# DDS9m-Controller.net
KiCad netlist of a schematic drawn in EAGLE
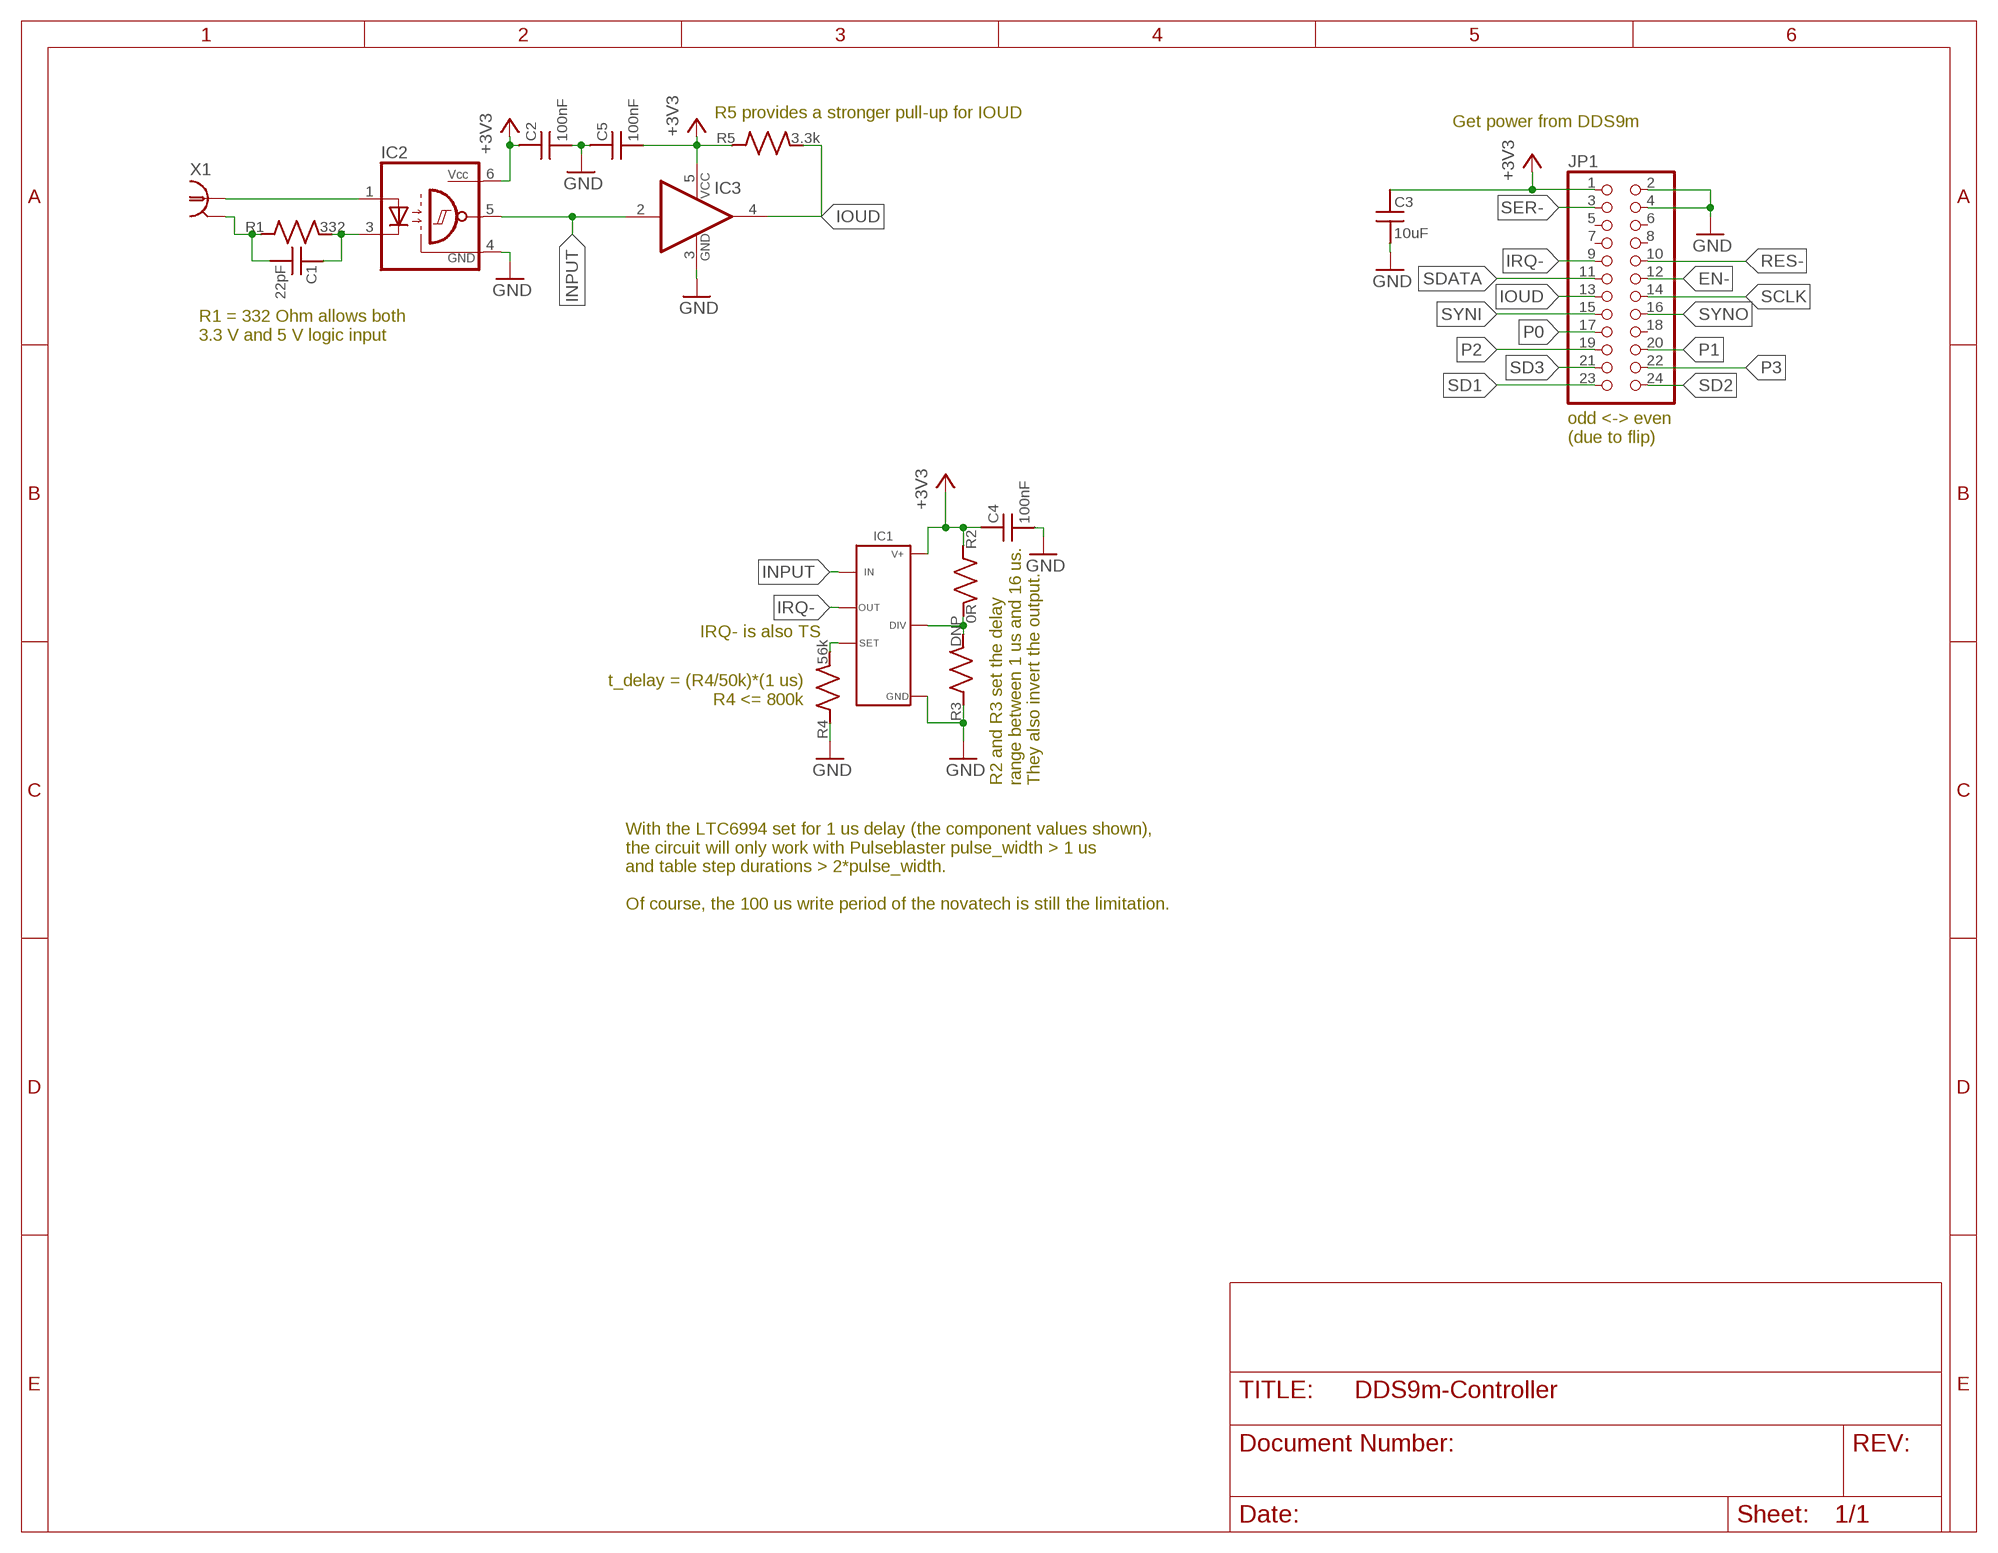
[diagram p0: schematic, sheet 1]

(export (version "E")
  (design (tool "Eeschema 10.0.6"))
  (components
    (comp (ref "C1")
      (value "22pF")
      (footprint "eagle-import:C_MLCC_0402")
      (fields (field (name "PARTNO") "CL05C220JB51PNC"))
      (libsource (lib "eagle-import") (part "C_MLCC_SMDCMLCC_0402"))
    )
    (comp (ref "C2")
      (value "100nF")
      (footprint "eagle-import:C_MLCC_0603")
      (fields (field (name "PARTNO") "CL10B104KB8NNNC"))
      (libsource (lib "eagle-import") (part "C_MLCC_SMDCMLCC_0603"))
    )
    (comp (ref "C3")
      (value "10uF")
      (footprint "eagle-import:C_MLCC_1210")
      (fields (field (name "PARTNO") "CL32B106KLJNNNE"))
      (libsource (lib "eagle-import") (part "C_MLCC_SMDCMLCC_1210"))
    )
    (comp (ref "C4")
      (value "100nF")
      (footprint "eagle-import:C_MLCC_0603")
      (fields (field (name "PARTNO") "CL10B104KB8NNNC"))
      (libsource (lib "eagle-import") (part "C_MLCC_SMDCMLCC_0603"))
    )
    (comp (ref "C5")
      (value "100nF")
      (footprint "eagle-import:C_MLCC_0603")
      (fields (field (name "PARTNO") "CL10B104KB8NNNC"))
      (libsource (lib "eagle-import") (part "C_MLCC_SMDCMLCC_0603"))
    )
    (comp (ref "IC1")
      (value "LTC6994-X")
      (footprint "eagle-import:SOT23-6L")
      (fields (field (name "PARTNO") "LTC6994IS6-2#TRMPBF"))
      (libsource (lib "eagle-import") (part "LTC6994-X"))
    )
    (comp (ref "IC2")
      (value "TLP2767")
      (footprint "eagle-import:SO6L")
      (fields (field (name "PARTNO") "TLP2767(TP,E"))
      (libsource (lib "eagle-import") (part "TLP2767"))
    )
    (comp (ref "IC3")
      (value "74LVC1G07DCK")
      (footprint "eagle-import:SC70-5")
      (fields (field (name "PARTNO") "SN74LVC1G07DCKR"))
      (libsource (lib "eagle-import") (part "741G07DCKLVC"))
    )
    (comp (ref "JP1")
      (value "PINHD-2X12")
      (footprint "eagle-import:2X12")
      (fields (field (name "PARTNO") "PPPC122LFBN-RC"))
      (libsource (lib "eagle-import") (part "PINHD-2X12"))
    )
    (comp (ref "R1")
      (value "332")
      (footprint "eagle-import:R_0603")
      (fields (field (name "PARTNO") "ERJ-3EKF3320V"))
      (libsource (lib "eagle-import") (part "R_SMDR0603"))
    )
    (comp (ref "R2")
      (value "0R")
      (footprint "eagle-import:R_0603")
      (fields (field (name "PARTNO") "MF-RES-0603-0"))
      (libsource (lib "eagle-import") (part "R_SMDR0603"))
    )
    (comp (ref "R3")
      (value "DNP")
      (footprint "eagle-import:R_0603")
      (libsource (lib "eagle-import") (part "R_SMDR0603"))
    )
    (comp (ref "R4")
      (value "56k")
      (footprint "eagle-import:R_0603")
      (fields (field (name "PARTNO") "ERA-3AEB563V"))
      (libsource (lib "eagle-import") (part "R_SMDR0603"))
    )
    (comp (ref "R5")
      (value "3.3k")
      (footprint "eagle-import:R_0603")
      (fields (field (name "PARTNO") "ERJ-3EKF3301V"))
      (libsource (lib "eagle-import") (part "R_SMDR0603"))
    )
    (comp (ref "X1")
      (value "BNC-V")
      (footprint "eagle-import:BNC-V")
      (fields (field (name "PARTNO") "5227222-3"))
      (libsource (lib "eagle-import") (part "BNC-V"))
    )
  )
  (nets
    (net (code "1") (name "+3V3") (class "Default")
      (node (ref "C2") (pin "P$1") (pinfunction "1_P$1") (pintype "passive"))
      (node (ref "C3") (pin "P$1") (pinfunction "1_P$1") (pintype "passive"))
      (node (ref "C4") (pin "P$1") (pinfunction "1_P$1") (pintype "passive"))
      (node (ref "C5") (pin "P$2") (pinfunction "2_P$2") (pintype "passive"))
      (node (ref "IC1") (pin "5") (pinfunction "V+_5") (pintype "input"))
      (node (ref "IC2") (pin "6") (pinfunction "VCC_6") (pintype "passive"))
      (node (ref "IC3") (pin "5") (pinfunction "VCC_5") (pintype "power_in"))
      (node (ref "JP1") (pin "1") (pinfunction "1_1") (pintype "passive"))
      (node (ref "R2") (pin "P$1") (pinfunction "1_P$1") (pintype "passive"))
      (node (ref "R5") (pin "P$1") (pinfunction "1_P$1") (pintype "passive"))
    )
    (net (code "2") (name "EN-") (class "Default")
      (node (ref "JP1") (pin "12") (pinfunction "12_12") (pintype "passive"))
    )
    (net (code "3") (name "GND") (class "Default")
      (node (ref "C2") (pin "P$2") (pinfunction "2_P$2") (pintype "passive"))
      (node (ref "C3") (pin "P$2") (pinfunction "2_P$2") (pintype "passive"))
      (node (ref "C4") (pin "P$2") (pinfunction "2_P$2") (pintype "passive"))
      (node (ref "C5") (pin "P$1") (pinfunction "1_P$1") (pintype "passive"))
      (node (ref "IC1") (pin "2") (pinfunction "GND_2") (pintype "input"))
      (node (ref "IC2") (pin "4") (pinfunction "GND_4") (pintype "passive"))
      (node (ref "IC3") (pin "3") (pinfunction "GND_3") (pintype "power_in"))
      (node (ref "JP1") (pin "2") (pinfunction "2_2") (pintype "passive"))
      (node (ref "JP1") (pin "4") (pinfunction "4_4") (pintype "passive"))
      (node (ref "R3") (pin "P$1") (pinfunction "1_P$1") (pintype "passive"))
      (node (ref "R4") (pin "P$1") (pinfunction "1_P$1") (pintype "passive"))
    )
    (net (code "4") (name "INPUT") (class "Default")
      (node (ref "IC1") (pin "1") (pinfunction "IN_1") (pintype "input"))
      (node (ref "IC2") (pin "5") (pinfunction "OUT_5") (pintype "passive"))
      (node (ref "IC3") (pin "2") (pinfunction "I_2") (pintype "input"))
    )
    (net (code "5") (name "IOUD") (class "Default")
      (node (ref "IC3") (pin "4") (pinfunction "O_4") (pintype "open_collector"))
      (node (ref "JP1") (pin "13") (pinfunction "13_13") (pintype "passive"))
      (node (ref "R5") (pin "P$2") (pinfunction "2_P$2") (pintype "passive"))
    )
    (net (code "6") (name "IRQ-") (class "Default")
      (node (ref "IC1") (pin "6") (pinfunction "OUT_6") (pintype "output"))
      (node (ref "JP1") (pin "9") (pinfunction "9_9") (pintype "passive"))
    )
    (net (code "7") (name "Net-(C1-1)") (class "Default")
      (node (ref "C1") (pin "P$1") (pinfunction "1_P$1") (pintype "passive"))
      (node (ref "IC2") (pin "3") (pinfunction "C_3") (pintype "passive"))
      (node (ref "R1") (pin "P$2") (pinfunction "2_P$2") (pintype "passive"))
    )
    (net (code "8") (name "Net-(C1-2)") (class "Default")
      (node (ref "C1") (pin "P$2") (pinfunction "2_P$2") (pintype "passive"))
      (node (ref "R1") (pin "P$1") (pinfunction "1_P$1") (pintype "passive"))
      (node (ref "X1") (pin "2") (pinfunction "2_2") (pintype "passive"))
    )
    (net (code "9") (name "Net-(IC1-DIV)") (class "Default")
      (node (ref "IC1") (pin "4") (pinfunction "DIV_4") (pintype "input"))
      (node (ref "R2") (pin "P$2") (pinfunction "2_P$2") (pintype "passive"))
      (node (ref "R3") (pin "P$2") (pinfunction "2_P$2") (pintype "passive"))
    )
    (net (code "10") (name "Net-(IC1-SET)") (class "Default")
      (node (ref "IC1") (pin "3") (pinfunction "SET_3") (pintype "input"))
      (node (ref "R4") (pin "P$2") (pinfunction "2_P$2") (pintype "passive"))
    )
    (net (code "11") (name "Net-(IC2-A)") (class "Default")
      (node (ref "IC2") (pin "1") (pinfunction "A_1") (pintype "passive"))
      (node (ref "X1") (pin "1") (pinfunction "1_1") (pintype "passive"))
    )
    (net (code "12") (name "P0") (class "Default")
      (node (ref "JP1") (pin "17") (pinfunction "17_17") (pintype "passive"))
    )
    (net (code "13") (name "P1") (class "Default")
      (node (ref "JP1") (pin "20") (pinfunction "20_20") (pintype "passive"))
    )
    (net (code "14") (name "P2") (class "Default")
      (node (ref "JP1") (pin "19") (pinfunction "19_19") (pintype "passive"))
    )
    (net (code "15") (name "P3") (class "Default")
      (node (ref "JP1") (pin "22") (pinfunction "22_22") (pintype "passive"))
    )
    (net (code "16") (name "RES-") (class "Default")
      (node (ref "JP1") (pin "10") (pinfunction "10_10") (pintype "passive"))
    )
    (net (code "17") (name "SCLK") (class "Default")
      (node (ref "JP1") (pin "14") (pinfunction "14_14") (pintype "passive"))
    )
    (net (code "18") (name "SD1") (class "Default")
      (node (ref "JP1") (pin "23") (pinfunction "23_23") (pintype "passive"))
    )
    (net (code "19") (name "SD2") (class "Default")
      (node (ref "JP1") (pin "24") (pinfunction "24_24") (pintype "passive"))
    )
    (net (code "20") (name "SD3") (class "Default")
      (node (ref "JP1") (pin "21") (pinfunction "21_21") (pintype "passive"))
    )
    (net (code "21") (name "SDATA") (class "Default")
      (node (ref "JP1") (pin "11") (pinfunction "11_11") (pintype "passive"))
    )
    (net (code "22") (name "SER-") (class "Default")
      (node (ref "JP1") (pin "3") (pinfunction "3_3") (pintype "passive"))
    )
    (net (code "23") (name "SYNI") (class "Default")
      (node (ref "JP1") (pin "15") (pinfunction "15_15") (pintype "passive"))
    )
    (net (code "24") (name "SYNO") (class "Default")
      (node (ref "JP1") (pin "16") (pinfunction "16_16") (pintype "passive"))
    )
    (net (code "25") (name "unconnected-(JP1-Pad5)") (class "Default")
      (node (ref "JP1") (pin "5") (pinfunction "5_5") (pintype "passive"))
    )
    (net (code "26") (name "unconnected-(JP1-Pad6)") (class "Default")
      (node (ref "JP1") (pin "6") (pinfunction "6_6") (pintype "passive"))
    )
    (net (code "27") (name "unconnected-(JP1-Pad7)") (class "Default")
      (node (ref "JP1") (pin "7") (pinfunction "7_7") (pintype "passive"))
    )
    (net (code "28") (name "unconnected-(JP1-Pad8)") (class "Default")
      (node (ref "JP1") (pin "8") (pinfunction "8_8") (pintype "passive"))
    )
    (net (code "29") (name "unconnected-(JP1-Pad18)") (class "Default")
      (node (ref "JP1") (pin "18") (pinfunction "18_18") (pintype "passive"))
    )
  )
)
